# Sheet2.net
KiCad netlist of a schematic drawn in Altium Designer
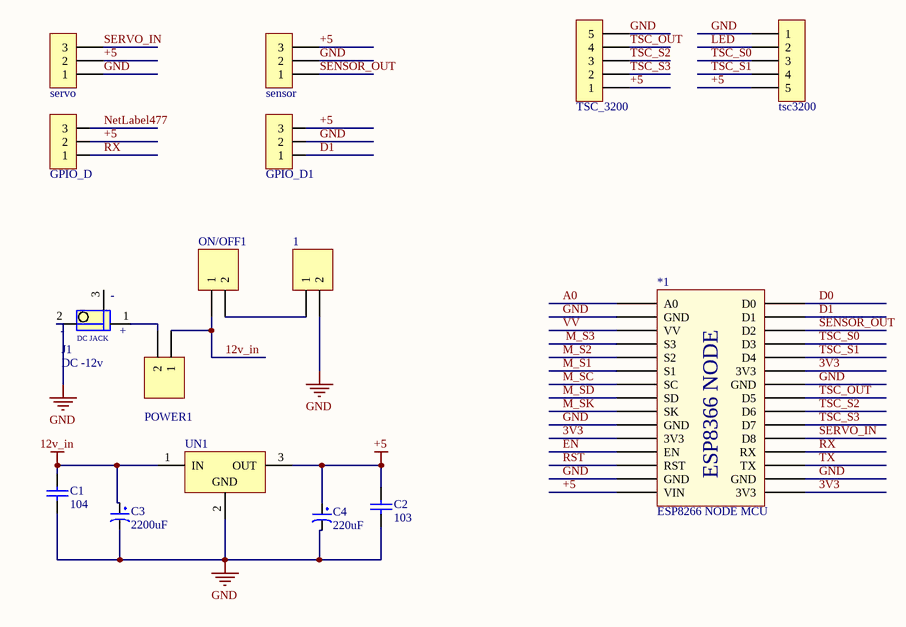
[diagram p0: Sheet2.SchDoc]

(export (version "E")
  (design (tool "Eeschema 10.0.6"))
  (components
    (comp (ref "*1")
      (value "ESP8266 NODE MCU")
      (footprint "ESP8266 NODE MCU")
      (libsource (lib "Altium_Lib_by_KhueNguyenCreator") (part "ESP8266 NODE MCU"))
    )
    (comp (ref "1")
      (value "Header 2_1")
      (footprint "HED2")
      (description "Header, 2-Pin")
      (fields (field (name "MANUFACTURER") "Generic Components"))
      (libsource (lib "") (part "Header 2_1_1"))
    )
    (comp (ref "C1")
      (value "104")
      (footprint "tu gom")
      (description "Cắm")
      (libsource (lib "Altium_Lib_by_KhueNguyenCreator") (part "Tu gom 104 50V"))
    )
    (comp (ref "C2")
      (value "103")
      (footprint "tu gom")
      (description "Cắm")
      (libsource (lib "Altium_Lib_by_KhueNguyenCreator") (part "Tu gom 103 50V"))
    )
    (comp (ref "C3")
      (value "2200uF")
      (footprint "tu hoa 10mm")
      (description "Cắm")
      (libsource (lib "Altium_Lib_by_KhueNguyenCreator") (part "Tu Hoa 2200uF 16V 10x20"))
    )
    (comp (ref "C4")
      (value "220uF")
      (footprint "tu hoa 6.5mm")
      (description "Cắm")
      (libsource (lib "Altium_Lib_by_KhueNguyenCreator") (part "Tu Hoa 220uF 16V 7x11"))
    )
    (comp (ref "H1")
      (value "TSC_3200")
      (footprint "XH2.54M-5")
      (description "Cắm")
      (libsource (lib "") (part "Header 5P 2.54 Duc Thang_1"))
    )
    (comp (ref "H2")
      (value "tsc3200")
      (footprint "XH2.54M-5")
      (description "Cắm")
      (libsource (lib "Altium_Lib_by_KhueNguyenCreator") (part "Header 5P 2.54 Duc Thang"))
    )
    (comp (ref "H3")
      (value "servo")
      (footprint "XH2.54M-3")
      (description "Cắm")
      (libsource (lib "Altium_Lib_by_KhueNguyenCreator") (part "Header 3P 2.54 Duc Thang"))
    )
    (comp (ref "H4")
      (value "sensor")
      (footprint "XH2.54M-3")
      (description "Cắm")
      (libsource (lib "Altium_Lib_by_KhueNguyenCreator") (part "Header 3P 2.54 Duc Thang"))
    )
    (comp (ref "J1")
      (value "DC -12v")
      (footprint "CON3_129_PJ-002A_TH_RA")
      (description "3 Pins, 1 Row 228mil Pitch, right angle Connector, male")
      (fields (field (name "MANUFACTURER") "JST") (field (name "MANUFACTURER PART NUMBER") "PJ-002A"))
      (libsource (lib "Altium_Lib_by_KhueNguyenCreator") (part "CON-PLG_3X1-228-DC_JACK"))
    )
    (comp (ref "JP1")
      (value "GPIO_D")
      (footprint "JP 1x3 DT")
      (description "Cắm")
      (libsource (lib "Altium_Lib_by_KhueNguyenCreator") (part "JP 1x3 2.54 Duc Thang"))
    )
    (comp (ref "JP2")
      (value "GPIO_D1")
      (footprint "JP 1x3 DT")
      (description "Cắm")
      (libsource (lib "Altium_Lib_by_KhueNguyenCreator") (part "JP 1x3 2.54 Duc Thang"))
    )
    (comp (ref "ON/OFF1")
      (value "Header 2_1")
      (footprint "HED2")
      (description "Header, 2-Pin")
      (fields (field (name "MANUFACTURER") "Generic Components"))
      (libsource (lib "") (part "Header 2_1_1"))
    )
    (comp (ref "POWER1")
      (value "Header 2_1")
      (footprint "HED2")
      (description "Header, 2-Pin")
      (fields (field (name "MANUFACTURER") "Generic Components"))
      (libsource (lib "syhaunguyen") (part "Header 2_1"))
    )
    (comp (ref "UN1")
      (value "L78M05CP")
      (footprint "QTO-220H2")
      (description "Positive Voltage Regulator")
      (fields (field (name "PUBLISHER") "Altium Limited"))
      (libsource (lib "syhaunguyen") (part "L78M05CP"))
    )
  )
  (nets
    (net (code "1") (name "+5") (class "Default")
      (node (ref "*1") (pin "15") (pinfunction "VIN_15") (pintype "passive"))
      (node (ref "C2") (pin "1") (pinfunction "1_1") (pintype "passive"))
      (node (ref "C4") (pin "1") (pinfunction "1_1") (pintype "passive"))
      (node (ref "H1") (pin "1") (pinfunction "1_1") (pintype "passive"))
      (node (ref "H2") (pin "5") (pinfunction "5_5") (pintype "passive"))
      (node (ref "H3") (pin "2") (pinfunction "2_2") (pintype "passive"))
      (node (ref "H4") (pin "3") (pinfunction "3_3") (pintype "passive"))
      (node (ref "JP1") (pin "2") (pinfunction "2_2") (pintype "passive"))
      (node (ref "JP2") (pin "3") (pinfunction "3_3") (pintype "passive"))
      (node (ref "UN1") (pin "3") (pinfunction "OUT_3") (pintype "power_in"))
    )
    (net (code "2") (name "/ M_S3") (class "Default")
      (node (ref "*1") (pin "4") (pinfunction "S3_4") (pintype "passive"))
    )
    (net (code "3") (name "/3V3") (class "Default")
      (node (ref "*1") (pin "11") (pinfunction "3V3_11") (pintype "passive"))
      (node (ref "*1") (pin "16") (pinfunction "3V3_16") (pintype "passive"))
      (node (ref "*1") (pin "25") (pinfunction "3V3_25") (pintype "passive"))
    )
    (net (code "4") (name "/A0") (class "Default")
      (node (ref "*1") (pin "1") (pinfunction "A0_1") (pintype "passive"))
    )
    (net (code "5") (name "/D0") (class "Default")
      (node (ref "*1") (pin "30") (pinfunction "D0_30") (pintype "passive"))
    )
    (net (code "6") (name "/D1") (class "Default")
      (node (ref "*1") (pin "29") (pinfunction "D1_29") (pintype "passive"))
      (node (ref "JP2") (pin "1") (pinfunction "1_1") (pintype "passive"))
    )
    (net (code "7") (name "/EN") (class "Default")
      (node (ref "*1") (pin "12") (pinfunction "EN_12") (pintype "passive"))
    )
    (net (code "8") (name "/LED") (class "Default")
      (node (ref "H2") (pin "2") (pinfunction "2_2") (pintype "passive"))
    )
    (net (code "9") (name "/M_S1") (class "Default")
      (node (ref "*1") (pin "6") (pinfunction "S1_6") (pintype "passive"))
    )
    (net (code "10") (name "/M_S2") (class "Default")
      (node (ref "*1") (pin "5") (pinfunction "S2_5") (pintype "passive"))
    )
    (net (code "11") (name "/M_SC") (class "Default")
      (node (ref "*1") (pin "7") (pinfunction "SC_7") (pintype "passive"))
    )
    (net (code "12") (name "/M_SD") (class "Default")
      (node (ref "*1") (pin "8") (pinfunction "SD_8") (pintype "passive"))
    )
    (net (code "13") (name "/M_SK") (class "Default")
      (node (ref "*1") (pin "9") (pinfunction "SK_9") (pintype "passive"))
    )
    (net (code "14") (name "/NetLabel477") (class "Default")
      (node (ref "JP1") (pin "3") (pinfunction "3_3") (pintype "passive"))
    )
    (net (code "15") (name "/RST") (class "Default")
      (node (ref "*1") (pin "13") (pinfunction "RST_13") (pintype "passive"))
    )
    (net (code "16") (name "/RX") (class "Default")
      (node (ref "*1") (pin "19") (pinfunction "RX_19") (pintype "passive"))
      (node (ref "JP1") (pin "1") (pinfunction "1_1") (pintype "passive"))
    )
    (net (code "17") (name "/SENSOR_OUT") (class "Default")
      (node (ref "*1") (pin "28") (pinfunction "D2_28") (pintype "passive"))
      (node (ref "H4") (pin "1") (pinfunction "1_1") (pintype "passive"))
    )
    (net (code "18") (name "/SERVO_IN") (class "Default")
      (node (ref "*1") (pin "20") (pinfunction "D8_20") (pintype "passive"))
      (node (ref "H3") (pin "3") (pinfunction "3_3") (pintype "passive"))
    )
    (net (code "19") (name "/TSC_OUT") (class "Default")
      (node (ref "*1") (pin "23") (pinfunction "D5_23") (pintype "passive"))
      (node (ref "H1") (pin "4") (pinfunction "4_4") (pintype "passive"))
    )
    (net (code "20") (name "/TSC_S0") (class "Default")
      (node (ref "*1") (pin "27") (pinfunction "D3_27") (pintype "passive"))
      (node (ref "H2") (pin "3") (pinfunction "3_3") (pintype "passive"))
    )
    (net (code "21") (name "/TSC_S1") (class "Default")
      (node (ref "*1") (pin "26") (pinfunction "D4_26") (pintype "passive"))
      (node (ref "H2") (pin "4") (pinfunction "4_4") (pintype "passive"))
    )
    (net (code "22") (name "/TSC_S2") (class "Default")
      (node (ref "*1") (pin "22") (pinfunction "D6_22") (pintype "passive"))
      (node (ref "H1") (pin "3") (pinfunction "3_3") (pintype "passive"))
    )
    (net (code "23") (name "/TSC_S3") (class "Default")
      (node (ref "*1") (pin "21") (pinfunction "D7_21") (pintype "passive"))
      (node (ref "H1") (pin "2") (pinfunction "2_2") (pintype "passive"))
    )
    (net (code "24") (name "/TX") (class "Default")
      (node (ref "*1") (pin "18") (pinfunction "TX_18") (pintype "passive"))
    )
    (net (code "25") (name "/VV") (class "Default")
      (node (ref "*1") (pin "3") (pinfunction "VV_3") (pintype "passive"))
    )
    (net (code "26") (name "12v_in") (class "Default")
      (node (ref "C1") (pin "1") (pinfunction "1_1") (pintype "passive"))
      (node (ref "C3") (pin "1") (pinfunction "1_1") (pintype "passive"))
      (node (ref "ON/OFF1") (pin "1") (pinfunction "1_1") (pintype "passive"))
      (node (ref "POWER1") (pin "1") (pinfunction "1_1") (pintype "passive"))
      (node (ref "UN1") (pin "1") (pinfunction "IN_1") (pintype "power_in"))
    )
    (net (code "27") (name "GND") (class "Default")
      (node (ref "*1") (pin "10") (pinfunction "GND_10") (pintype "passive"))
      (node (ref "*1") (pin "14") (pinfunction "GND_14") (pintype "passive"))
      (node (ref "*1") (pin "17") (pinfunction "GND_17") (pintype "passive"))
      (node (ref "*1") (pin "2") (pinfunction "GND_2") (pintype "passive"))
      (node (ref "*1") (pin "24") (pinfunction "GND_24") (pintype "passive"))
      (node (ref "1") (pin "2") (pinfunction "2_2") (pintype "passive"))
      (node (ref "C1") (pin "2") (pinfunction "2_2") (pintype "passive"))
      (node (ref "C2") (pin "2") (pinfunction "2_2") (pintype "passive"))
      (node (ref "C3") (pin "2") (pinfunction "2_2") (pintype "passive"))
      (node (ref "C4") (pin "2") (pinfunction "2_2") (pintype "passive"))
      (node (ref "H1") (pin "5") (pinfunction "5_5") (pintype "passive"))
      (node (ref "H2") (pin "1") (pinfunction "1_1") (pintype "passive"))
      (node (ref "H3") (pin "1") (pinfunction "1_1") (pintype "passive"))
      (node (ref "H4") (pin "2") (pinfunction "2_2") (pintype "passive"))
      (node (ref "J1") (pin "2") (pinfunction "2_2") (pintype "passive"))
      (node (ref "JP2") (pin "2") (pinfunction "2_2") (pintype "passive"))
      (node (ref "UN1") (pin "2") (pinfunction "GND_2") (pintype "power_in"))
    )
    (net (code "28") (name "Net-(1-Pad1)") (class "Default")
      (node (ref "1") (pin "1") (pinfunction "1_1") (pintype "passive"))
      (node (ref "ON/OFF1") (pin "2") (pinfunction "2_2") (pintype "passive"))
    )
    (net (code "29") (name "Net-(J1-Pad1)") (class "Default")
      (node (ref "J1") (pin "1") (pinfunction "1_1") (pintype "passive"))
      (node (ref "POWER1") (pin "2") (pinfunction "2_2") (pintype "passive"))
    )
    (net (code "30") (name "unconnected-(J1---Pad3)") (class "Default")
      (node (ref "J1") (pin "3") (pinfunction "-_3") (pintype "passive"))
    )
  )
)
